# B.net
KiCad netlist of a schematic drawn in Altium Designer
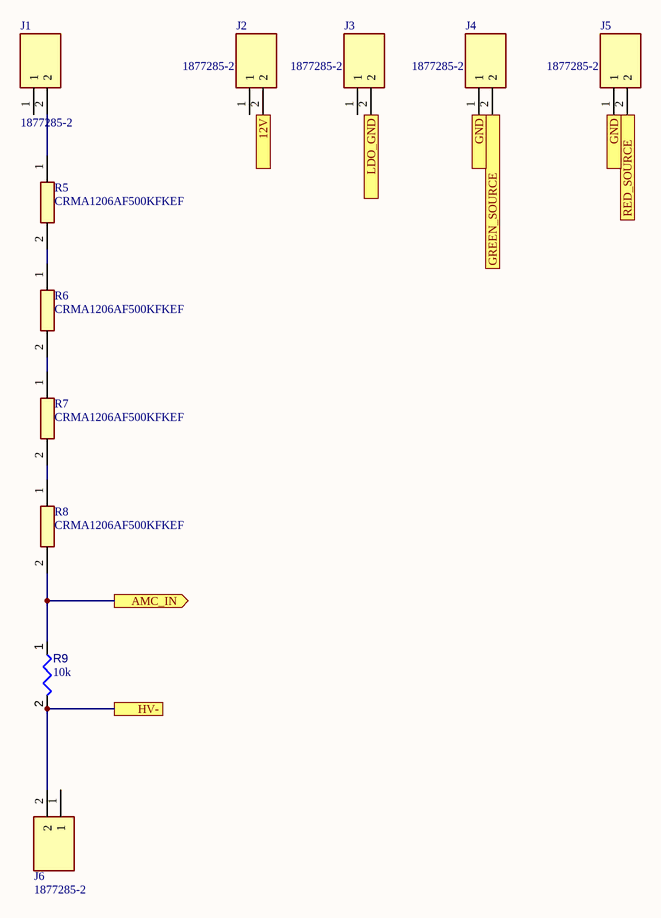
[diagram p0: B.SchDoc]

(export (version "E")
  (design (tool "Eeschema 10.0.6"))
  (components
    (comp (ref "J1")
      (value "1877285-2")
      (footprint "18772852")
      (description "Connector")
      (fields (field (name "MOUSER PART NUMBER") "571-1877285-2"))
      (libsource (lib "SamacSys") (part "1877285-2"))
    )
    (comp (ref "J2")
      (value "1877285-2")
      (footprint "18772852")
      (description "Connector")
      (fields (field (name "MOUSER PART NUMBER") "571-1877285-2"))
      (libsource (lib "SamacSys") (part "1877285-2"))
    )
    (comp (ref "J3")
      (value "1877285-2")
      (footprint "18772852")
      (description "Connector")
      (fields (field (name "MOUSER PART NUMBER") "571-1877285-2"))
      (libsource (lib "SamacSys") (part "1877285-2"))
    )
    (comp (ref "J4")
      (value "1877285-2")
      (footprint "18772852")
      (description "Connector")
      (fields (field (name "MOUSER PART NUMBER") "571-1877285-2"))
      (libsource (lib "SamacSys") (part "1877285-2"))
    )
    (comp (ref "J5")
      (value "1877285-2")
      (footprint "18772852")
      (description "Connector")
      (fields (field (name "MOUSER PART NUMBER") "571-1877285-2"))
      (libsource (lib "SamacSys") (part "1877285-2"))
    )
    (comp (ref "J6")
      (value "1877285-2")
      (footprint "18772852")
      (description "Connector")
      (fields (field (name "MOUSER PART NUMBER") "571-1877285-2"))
      (libsource (lib "") (part "1877285-2_1"))
    )
    (comp (ref "R5")
      (value "CRMA1206AF500KFKEF")
      (footprint "SamacSys:RESC3216X74N")
      (description "Resistor")
      (fields (field (name "MOUSER PART NUMBER") "71-CRMA1206AF500KFKF"))
      (libsource (lib "*") (part "CRMA1206AF500KFKEF"))
    )
    (comp (ref "R6")
      (value "CRMA1206AF500KFKEF")
      (footprint "SamacSys:RESC3216X74N")
      (description "Resistor")
      (fields (field (name "MOUSER PART NUMBER") "71-CRMA1206AF500KFKF"))
      (libsource (lib "*") (part "CRMA1206AF500KFKEF"))
    )
    (comp (ref "R7")
      (value "CRMA1206AF500KFKEF")
      (footprint "SamacSys:RESC3216X74N")
      (description "Resistor")
      (fields (field (name "MOUSER PART NUMBER") "71-CRMA1206AF500KFKF"))
      (libsource (lib "*") (part "CRMA1206AF500KFKEF"))
    )
    (comp (ref "R8")
      (value "CRMA1206AF500KFKEF")
      (footprint "SamacSys:RESC3216X74N")
      (description "Resistor")
      (fields (field (name "MOUSER PART NUMBER") "71-CRMA1206AF500KFKF"))
      (libsource (lib "*") (part "CRMA1206AF500KFKEF"))
    )
    (comp (ref "R9")
      (value "10k")
      (footprint "RESC2013X50X35ML15T15")
      (description "Chip Resistor, 10 KOhm, +/- 1%, 125 mW, -55 to 155 degC, 0805 (2012 Metric)")
      (fields (field (name "TOLERANCE") "1%") (field (name "POWER") "125mW"))
      (libsource (lib "Hector Dela Rosa") (part "RES-2"))
    )
  )
  (nets
    (net (code "1") (name "/12V") (class "Default")
      (node (ref "J2") (pin "2") (pinfunction "2_2") (pintype "passive"))
    )
    (net (code "2") (name "/AMC_IN") (class "Default")
      (node (ref "R8") (pin "2") (pinfunction "2_2") (pintype "passive"))
      (node (ref "R9") (pin "1") (pinfunction "1_1") (pintype "passive"))
    )
    (net (code "3") (name "/GND") (class "Default")
      (node (ref "J4") (pin "1") (pinfunction "1_1") (pintype "passive"))
      (node (ref "J5") (pin "1") (pinfunction "1_1") (pintype "passive"))
    )
    (net (code "4") (name "/GREEN_SOURCE") (class "Default")
      (node (ref "J4") (pin "2") (pinfunction "2_2") (pintype "passive"))
    )
    (net (code "5") (name "/HV-") (class "Default")
      (node (ref "J6") (pin "2") (pinfunction "2_2") (pintype "passive"))
      (node (ref "R9") (pin "2") (pinfunction "2_2") (pintype "passive"))
    )
    (net (code "6") (name "/LDO_GND") (class "Default")
      (node (ref "J3") (pin "2") (pinfunction "2_2") (pintype "passive"))
    )
    (net (code "7") (name "/RED_SOURCE") (class "Default")
      (node (ref "J5") (pin "2") (pinfunction "2_2") (pintype "passive"))
    )
    (net (code "8") (name "Net-(J1-Pad2)") (class "Default")
      (node (ref "J1") (pin "2") (pinfunction "2_2") (pintype "passive"))
      (node (ref "R5") (pin "1") (pinfunction "1_1") (pintype "passive"))
    )
    (net (code "9") (name "Net-(R5-Pad2)") (class "Default")
      (node (ref "R5") (pin "2") (pinfunction "2_2") (pintype "passive"))
      (node (ref "R6") (pin "1") (pinfunction "1_1") (pintype "passive"))
    )
    (net (code "10") (name "Net-(R6-Pad2)") (class "Default")
      (node (ref "R6") (pin "2") (pinfunction "2_2") (pintype "passive"))
      (node (ref "R7") (pin "1") (pinfunction "1_1") (pintype "passive"))
    )
    (net (code "11") (name "Net-(R7-Pad2)") (class "Default")
      (node (ref "R7") (pin "2") (pinfunction "2_2") (pintype "passive"))
      (node (ref "R8") (pin "1") (pinfunction "1_1") (pintype "passive"))
    )
    (net (code "12") (name "unconnected-(J1-Pad1)") (class "Default")
      (node (ref "J1") (pin "1") (pinfunction "1_1") (pintype "passive"))
    )
    (net (code "13") (name "unconnected-(J2-Pad1)") (class "Default")
      (node (ref "J2") (pin "1") (pinfunction "1_1") (pintype "passive"))
    )
    (net (code "14") (name "unconnected-(J3-Pad1)") (class "Default")
      (node (ref "J3") (pin "1") (pinfunction "1_1") (pintype "passive"))
    )
    (net (code "15") (name "unconnected-(J6-Pad1)") (class "Default")
      (node (ref "J6") (pin "1") (pinfunction "1_1") (pintype "passive"))
    )
  )
)
